# ResistorPatch2.net
KiCad netlist of a schematic drawn in Altium Designer
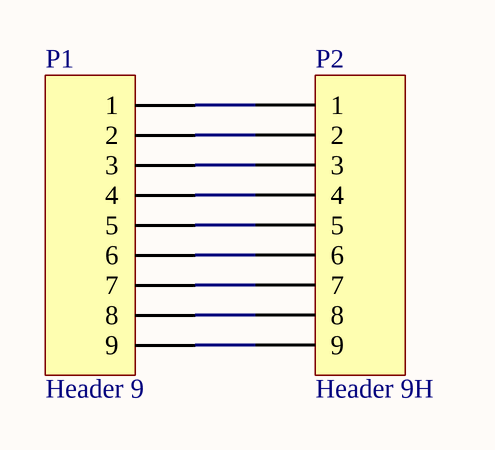
[diagram p0: ResistorPatch2.SchDoc]

(export (version "E")
  (design (tool "Eeschema 10.0.6"))
  (components
    (comp (ref "P1")
      (value "Header 9")
      (footprint "HDR1X9")
      (description "Header, 9-Pin")
      (fields (field (name "PUBLISHER") "Altium Limited"))
      (libsource (lib "Miscellaneous Connectors") (part "Header 9"))
    )
    (comp (ref "P2")
      (value "Header 9H")
      (footprint "HDR1X9H")
      (description "Header, 9-Pin, Right Angle")
      (fields (field (name "PUBLISHER") "Altium Limited"))
      (libsource (lib "Miscellaneous Connectors") (part "Header 9H"))
    )
  )
  (nets
    (net (code "1") (name "Net-(P1-Pad1)") (class "Default")
      (node (ref "P1") (pin "1") (pinfunction "1_1") (pintype "passive"))
      (node (ref "P2") (pin "1") (pinfunction "1_1") (pintype "passive"))
    )
    (net (code "2") (name "Net-(P1-Pad2)") (class "Default")
      (node (ref "P1") (pin "2") (pinfunction "2_2") (pintype "passive"))
      (node (ref "P2") (pin "2") (pinfunction "2_2") (pintype "passive"))
    )
    (net (code "3") (name "Net-(P1-Pad3)") (class "Default")
      (node (ref "P1") (pin "3") (pinfunction "3_3") (pintype "passive"))
      (node (ref "P2") (pin "3") (pinfunction "3_3") (pintype "passive"))
    )
    (net (code "4") (name "Net-(P1-Pad4)") (class "Default")
      (node (ref "P1") (pin "4") (pinfunction "4_4") (pintype "passive"))
      (node (ref "P2") (pin "4") (pinfunction "4_4") (pintype "passive"))
    )
    (net (code "5") (name "Net-(P1-Pad5)") (class "Default")
      (node (ref "P1") (pin "5") (pinfunction "5_5") (pintype "passive"))
      (node (ref "P2") (pin "5") (pinfunction "5_5") (pintype "passive"))
    )
    (net (code "6") (name "Net-(P1-Pad6)") (class "Default")
      (node (ref "P1") (pin "6") (pinfunction "6_6") (pintype "passive"))
      (node (ref "P2") (pin "6") (pinfunction "6_6") (pintype "passive"))
    )
    (net (code "7") (name "Net-(P1-Pad7)") (class "Default")
      (node (ref "P1") (pin "7") (pinfunction "7_7") (pintype "passive"))
      (node (ref "P2") (pin "7") (pinfunction "7_7") (pintype "passive"))
    )
    (net (code "8") (name "Net-(P1-Pad8)") (class "Default")
      (node (ref "P1") (pin "8") (pinfunction "8_8") (pintype "passive"))
      (node (ref "P2") (pin "8") (pinfunction "8_8") (pintype "passive"))
    )
    (net (code "9") (name "Net-(P1-Pad9)") (class "Default")
      (node (ref "P1") (pin "9") (pinfunction "9_9") (pintype "passive"))
      (node (ref "P2") (pin "9") (pinfunction "9_9") (pintype "passive"))
    )
  )
)
